# USB_RS485.net
KiCad netlist of a schematic drawn in EAGLE
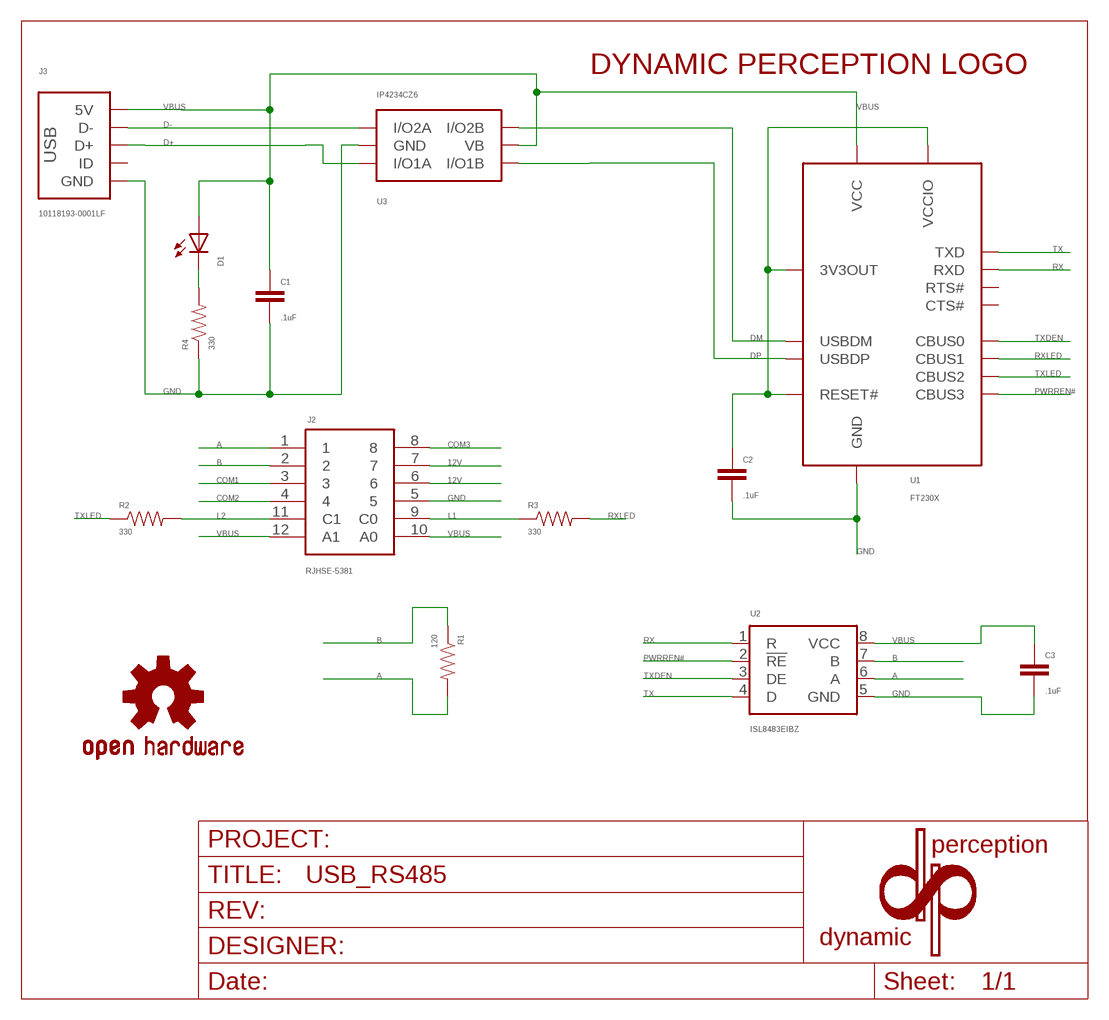
[diagram p0: schematic, sheet 1]

(export (version "E")
  (design (tool "Eeschema 10.0.6"))
  (components
    (comp (ref "C1")
      (value ".1uF")
      (footprint "eagle-import:0402_CAP")
      (libsource (lib "eagle-import") (part "CAP_NONPOL0402"))
    )
    (comp (ref "C2")
      (value ".1uF")
      (footprint "eagle-import:0402_CAP")
      (libsource (lib "eagle-import") (part "CAP_NONPOL0402"))
    )
    (comp (ref "C3")
      (value ".1uF")
      (footprint "eagle-import:0402_CAP")
      (libsource (lib "eagle-import") (part "CAP_NONPOL0402"))
    )
    (comp (ref "D1")
      (value "LEDSML0603")
      (footprint "eagle-import:SML0603")
      (libsource (lib "eagle-import") (part "LEDSML0603"))
    )
    (comp (ref "J2")
      (value "RJHSE-5381")
      (footprint "eagle-import:RIGHT_ANGLE")
      (libsource (lib "eagle-import") (part "RJHS-538X"))
    )
    (comp (ref "J3")
      (value "10118193-0001LF")
      (footprint "eagle-import:10118193-0001LF")
      (libsource (lib "eagle-import") (part "USB10118193-0001LF"))
    )
    (comp (ref "LOGO1")
      (value "DP_LOGOSMALL")
      (footprint "eagle-import:DP_LOGO_SMALL")
      (libsource (lib "eagle-import") (part "DP_LOGOSMALL"))
    )
    (comp (ref "R1")
      (value "120")
      (footprint "eagle-import:0402_RES")
      (libsource (lib "eagle-import") (part "RESISTOR0402"))
    )
    (comp (ref "R2")
      (value "330")
      (footprint "eagle-import:0402_RES")
      (libsource (lib "eagle-import") (part "RESISTOR0402"))
    )
    (comp (ref "R3")
      (value "330")
      (footprint "eagle-import:0402_RES")
      (libsource (lib "eagle-import") (part "RESISTOR0402"))
    )
    (comp (ref "R4")
      (value "330")
      (footprint "eagle-import:0402_RES")
      (libsource (lib "eagle-import") (part "RESISTOR0402"))
    )
    (comp (ref "U$1")
      (value "OSHW-LOGOS")
      (footprint "eagle-import:OSHW-LOGO-S")
      (libsource (lib "eagle-import") (part "OSHW-LOGOS"))
    )
    (comp (ref "U$2")
      (value "DP_FRAME")
      (footprint "eagle-import:DP_FRAME")
      (fields
        (field (name "DNAME") "PARKER DILLMANN")
        (field (name "PNAME") "USB -> RS485")
        (field (name "REVNUM") "8")
      )
      (libsource (lib "eagle-import") (part "DP_FRAME"))
    )
    (comp (ref "U1")
      (value "FT230X")
      (footprint "eagle-import:SSOP-16")
      (libsource (lib "eagle-import") (part "FT230XSSOP-16"))
    )
    (comp (ref "U2")
      (value "ISL8483EIBZ")
      (footprint "eagle-import:SO-08")
      (fields
        (field (name "MF") "TEXAS INSTRUMENTS")
        (field (name "MPN") "SN65176BD")
        (field (name "MF_1") "TEXAS INSTRUMENTS")
        (field (name "MPN_1") "SN65176BD")
        (field (name "OC_FARNELL") "9589970")
        (field (name "OC_NEWARK") "08F5891")
      )
      (libsource (lib "eagle-import") (part "SN65176D"))
    )
    (comp (ref "U3")
      (value "IP4234CZ6")
      (footprint "eagle-import:SOT-457")
      (libsource (lib "eagle-import") (part "IP4234CZ6SOT-457"))
    )
  )
  (nets
    (net (code "1") (name "/12V") (class "Default")
      (node (ref "J2") (pin "6") (pinfunction "6_6") (pintype "bidirectional"))
      (node (ref "J2") (pin "7") (pinfunction "7_7") (pintype "bidirectional"))
    )
    (net (code "2") (name "/A") (class "Default")
      (node (ref "J2") (pin "1") (pinfunction "1_1") (pintype "bidirectional"))
      (node (ref "R1") (pin "2") (pinfunction "2_2") (pintype "passive"))
      (node (ref "U2") (pin "6") (pinfunction "A_6") (pintype "input"))
    )
    (net (code "3") (name "/B") (class "Default")
      (node (ref "J2") (pin "2") (pinfunction "2_2") (pintype "bidirectional"))
      (node (ref "R1") (pin "1") (pinfunction "1_1") (pintype "passive"))
      (node (ref "U2") (pin "7") (pinfunction "B_7") (pintype "input"))
    )
    (net (code "4") (name "/COM1") (class "Default")
      (node (ref "J2") (pin "3") (pinfunction "3_3") (pintype "bidirectional"))
    )
    (net (code "5") (name "/COM2") (class "Default")
      (node (ref "J2") (pin "4") (pinfunction "4_4") (pintype "bidirectional"))
    )
    (net (code "6") (name "/COM3") (class "Default")
      (node (ref "J2") (pin "8") (pinfunction "8_8") (pintype "bidirectional"))
    )
    (net (code "7") (name "/D+") (class "Default")
      (node (ref "J3") (pin "3") (pinfunction "D+_3") (pintype "bidirectional"))
      (node (ref "U3") (pin "1") (pinfunction "I/O1A_1") (pintype "bidirectional"))
    )
    (net (code "8") (name "/D-") (class "Default")
      (node (ref "J3") (pin "2") (pinfunction "D-_2") (pintype "bidirectional"))
      (node (ref "U3") (pin "6") (pinfunction "I/O2A_6") (pintype "bidirectional"))
    )
    (net (code "9") (name "/DM") (class "Default")
      (node (ref "U1") (pin "9") (pinfunction "USBDM_9") (pintype "bidirectional"))
      (node (ref "U3") (pin "4") (pinfunction "I/O2B_4") (pintype "bidirectional"))
    )
    (net (code "10") (name "/DP") (class "Default")
      (node (ref "U1") (pin "8") (pinfunction "USBDP_8") (pintype "bidirectional"))
      (node (ref "U3") (pin "3") (pinfunction "I/O1B_3") (pintype "bidirectional"))
    )
    (net (code "11") (name "/GND") (class "Default")
      (node (ref "C1") (pin "2") (pinfunction "2_2") (pintype "passive"))
      (node (ref "C2") (pin "2") (pinfunction "2_2") (pintype "passive"))
      (node (ref "C3") (pin "2") (pinfunction "2_2") (pintype "passive"))
      (node (ref "J2") (pin "5") (pinfunction "5_5") (pintype "bidirectional"))
      (node (ref "J3") (pin "5") (pinfunction "GND_5") (pintype "bidirectional"))
      (node (ref "J3") (pin "S1") (pinfunction "GND_S1") (pintype "bidirectional"))
      (node (ref "J3") (pin "S2") (pinfunction "GND_S2") (pintype "bidirectional"))
      (node (ref "J3") (pin "S3") (pinfunction "GND_S3") (pintype "bidirectional"))
      (node (ref "J3") (pin "S4") (pinfunction "GND_S4") (pintype "bidirectional"))
      (node (ref "R4") (pin "1") (pinfunction "1_1") (pintype "passive"))
      (node (ref "U1") (pin "13") (pinfunction "GND_13") (pintype "bidirectional"))
      (node (ref "U1") (pin "5") (pinfunction "GND_5") (pintype "bidirectional"))
      (node (ref "U2") (pin "5") (pinfunction "GND_5") (pintype "input"))
      (node (ref "U3") (pin "2") (pinfunction "GND_2") (pintype "bidirectional"))
    )
    (net (code "12") (name "/L1") (class "Default")
      (node (ref "J2") (pin "9") (pinfunction "C0_9") (pintype "bidirectional"))
      (node (ref "R3") (pin "1") (pinfunction "1_1") (pintype "passive"))
    )
    (net (code "13") (name "/L2") (class "Default")
      (node (ref "J2") (pin "11") (pinfunction "C1_11") (pintype "bidirectional"))
      (node (ref "R2") (pin "2") (pinfunction "2_2") (pintype "passive"))
    )
    (net (code "14") (name "/PWRREN#") (class "Default")
      (node (ref "U1") (pin "16") (pinfunction "CBUS3_16") (pintype "bidirectional"))
      (node (ref "U2") (pin "2") (pinfunction "~{RE}_2") (pintype "input"))
    )
    (net (code "15") (name "/RX") (class "Default")
      (node (ref "U1") (pin "4") (pinfunction "RXD_4") (pintype "bidirectional"))
      (node (ref "U2") (pin "1") (pinfunction "R_1") (pintype "input"))
    )
    (net (code "16") (name "/RXLED") (class "Default")
      (node (ref "R3") (pin "2") (pinfunction "2_2") (pintype "passive"))
      (node (ref "U1") (pin "14") (pinfunction "CBUS1_14") (pintype "bidirectional"))
    )
    (net (code "17") (name "/TX") (class "Default")
      (node (ref "U1") (pin "1") (pinfunction "TXD_1") (pintype "bidirectional"))
      (node (ref "U2") (pin "4") (pinfunction "D_4") (pintype "input"))
    )
    (net (code "18") (name "/TXDEN") (class "Default")
      (node (ref "U1") (pin "15") (pinfunction "CBUS0_15") (pintype "bidirectional"))
      (node (ref "U2") (pin "3") (pinfunction "DE_3") (pintype "input"))
    )
    (net (code "19") (name "/TXLED") (class "Default")
      (node (ref "R2") (pin "1") (pinfunction "1_1") (pintype "passive"))
      (node (ref "U1") (pin "7") (pinfunction "CBUS2_7") (pintype "bidirectional"))
    )
    (net (code "20") (name "/VBUS") (class "Default")
      (node (ref "C1") (pin "1") (pinfunction "1_1") (pintype "passive"))
      (node (ref "C3") (pin "1") (pinfunction "1_1") (pintype "passive"))
      (node (ref "D1") (pin "A") (pinfunction "A_A") (pintype "passive"))
      (node (ref "J2") (pin "10") (pinfunction "A0_10") (pintype "bidirectional"))
      (node (ref "J2") (pin "12") (pinfunction "A1_12") (pintype "bidirectional"))
      (node (ref "J3") (pin "1") (pinfunction "5V_1") (pintype "bidirectional"))
      (node (ref "U1") (pin "12") (pinfunction "VCC_12") (pintype "bidirectional"))
      (node (ref "U2") (pin "8") (pinfunction "VCC_8") (pintype "input"))
      (node (ref "U3") (pin "5") (pinfunction "VB_5") (pintype "bidirectional"))
    )
    (net (code "21") (name "Net-(D1-PadC)") (class "Default")
      (node (ref "D1") (pin "C") (pinfunction "C_C") (pintype "passive"))
      (node (ref "R4") (pin "2") (pinfunction "2_2") (pintype "passive"))
    )
    (net (code "22") (name "Net-(U1-3V3OUT)") (class "Default")
      (node (ref "C2") (pin "1") (pinfunction "1_1") (pintype "passive"))
      (node (ref "U1") (pin "10") (pinfunction "3V3OUT_10") (pintype "bidirectional"))
      (node (ref "U1") (pin "11") (pinfunction "RESET#_11") (pintype "bidirectional"))
      (node (ref "U1") (pin "3") (pinfunction "VCCIO_3") (pintype "bidirectional"))
    )
    (net (code "23") (name "unconnected-(J3-ID-Pad4)") (class "Default")
      (node (ref "J3") (pin "4") (pinfunction "ID_4") (pintype "bidirectional"))
    )
    (net (code "24") (name "unconnected-(U1-CTS#-Pad6)") (class "Default")
      (node (ref "U1") (pin "6") (pinfunction "CTS#_6") (pintype "bidirectional"))
    )
    (net (code "25") (name "unconnected-(U1-RTS#-Pad2)") (class "Default")
      (node (ref "U1") (pin "2") (pinfunction "RTS#_2") (pintype "bidirectional"))
    )
  )
)
